# Ldo_6V5_5V0.net
KiCad netlist of a schematic drawn in Altium Designer
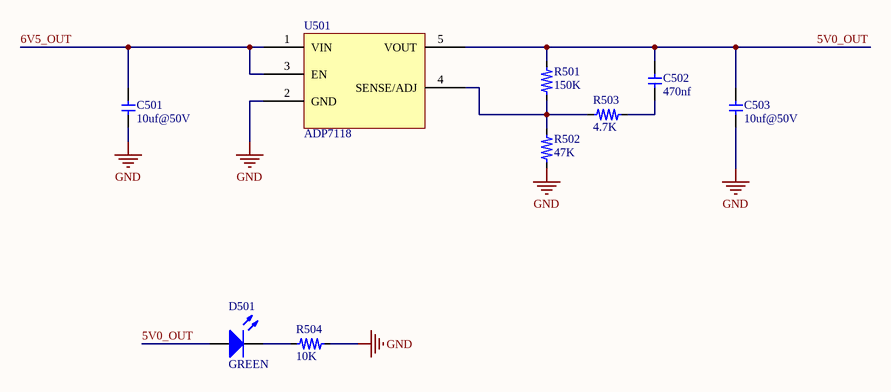
[diagram p0: Ldo.+6V5.+5V0.SchDoc]

(export (version "E")
  (design (tool "Eeschema 10.0.6"))
  (components
    (comp (ref "C501")
      (value "10uf@50V")
      (footprint "C1210")
      (fields (field (name "Comment") "Cap"))
      (libsource (lib "carrot_lib") (part "Cap"))
    )
    (comp (ref "C502")
      (value "470nf")
      (footprint "C0603")
      (fields (field (name "Comment") "Cap"))
      (libsource (lib "carrot_lib") (part "Cap"))
    )
    (comp (ref "C503")
      (value "10uf@50V")
      (footprint "C1210")
      (fields (field (name "Comment") "Cap"))
      (libsource (lib "carrot_lib") (part "Cap"))
    )
    (comp (ref "D501")
      (value "GREEN")
      (footprint "LED0603")
      (fields (field (name "Comment") "LED"))
      (libsource (lib "carrot_lib") (part "LED"))
    )
    (comp (ref "R501")
      (value "150K")
      (footprint "R0603")
      (description "电阻")
      (fields (field (name "Comment") "Res"))
      (libsource (lib "carrot_lib") (part "Res"))
    )
    (comp (ref "R502")
      (value "47K")
      (footprint "R0603")
      (description "电阻")
      (fields (field (name "Comment") "Res"))
      (libsource (lib "carrot_lib") (part "Res"))
    )
    (comp (ref "R503")
      (value "4.7K")
      (footprint "R0603")
      (description "电阻")
      (fields (field (name "Comment") "Res"))
      (libsource (lib "carrot_lib") (part "Res"))
    )
    (comp (ref "R504")
      (value "10K")
      (footprint "R0603")
      (description "电阻")
      (fields (field (name "Comment") "Res"))
      (libsource (lib "carrot_lib") (part "Res"))
    )
    (comp (ref "U501")
      (value "ADP7118")
      (footprint "ADP7118-TSOT5")
      (description "20 V, 200 mA, Low Noise,CMOS LDO Linear Regulator.")
      (libsource (lib "carrot_lib") (part "ADP7118AUJ"))
    )
  )
  (nets
    (net (code "1") (name "/5V0_OUT") (class "Default")
      (node (ref "C502") (pin "1") (pinfunction "1_1") (pintype "passive"))
      (node (ref "C503") (pin "2") (pinfunction "2_2") (pintype "passive"))
      (node (ref "D501") (pin "1") (pinfunction "A_1") (pintype "passive"))
      (node (ref "R501") (pin "2") (pinfunction "2_2") (pintype "passive"))
      (node (ref "U501") (pin "5") (pinfunction "VOUT_5") (pintype "passive"))
    )
    (net (code "2") (name "/6V5_OUT") (class "Default")
      (node (ref "C501") (pin "2") (pinfunction "2_2") (pintype "passive"))
      (node (ref "U501") (pin "1") (pinfunction "VIN_1") (pintype "passive"))
      (node (ref "U501") (pin "3") (pinfunction "EN_3") (pintype "passive"))
    )
    (net (code "3") (name "GND") (class "Default")
      (node (ref "C501") (pin "1") (pinfunction "1_1") (pintype "passive"))
      (node (ref "C503") (pin "1") (pinfunction "1_1") (pintype "passive"))
      (node (ref "R502") (pin "1") (pinfunction "1_1") (pintype "passive"))
      (node (ref "R504") (pin "1") (pinfunction "1_1") (pintype "passive"))
      (node (ref "U501") (pin "2") (pinfunction "GND_2") (pintype "passive"))
    )
    (net (code "4") (name "Net-(C502-Pad2)") (class "Default")
      (node (ref "C502") (pin "2") (pinfunction "2_2") (pintype "passive"))
      (node (ref "R503") (pin "1") (pinfunction "1_1") (pintype "passive"))
    )
    (net (code "5") (name "Net-(D501-K)") (class "Default")
      (node (ref "D501") (pin "2") (pinfunction "K_2") (pintype "passive"))
      (node (ref "R504") (pin "2") (pinfunction "2_2") (pintype "passive"))
    )
    (net (code "6") (name "Net-(U501-SENSE{slash}ADJ)") (class "Default")
      (node (ref "R501") (pin "1") (pinfunction "1_1") (pintype "passive"))
      (node (ref "R502") (pin "2") (pinfunction "2_2") (pintype "passive"))
      (node (ref "R503") (pin "2") (pinfunction "2_2") (pintype "passive"))
      (node (ref "U501") (pin "4") (pinfunction "SENSE/ADJ_4") (pintype "passive"))
    )
  )
)
